# Tiny84_board.net
KiCad netlist of a schematic drawn in EAGLE
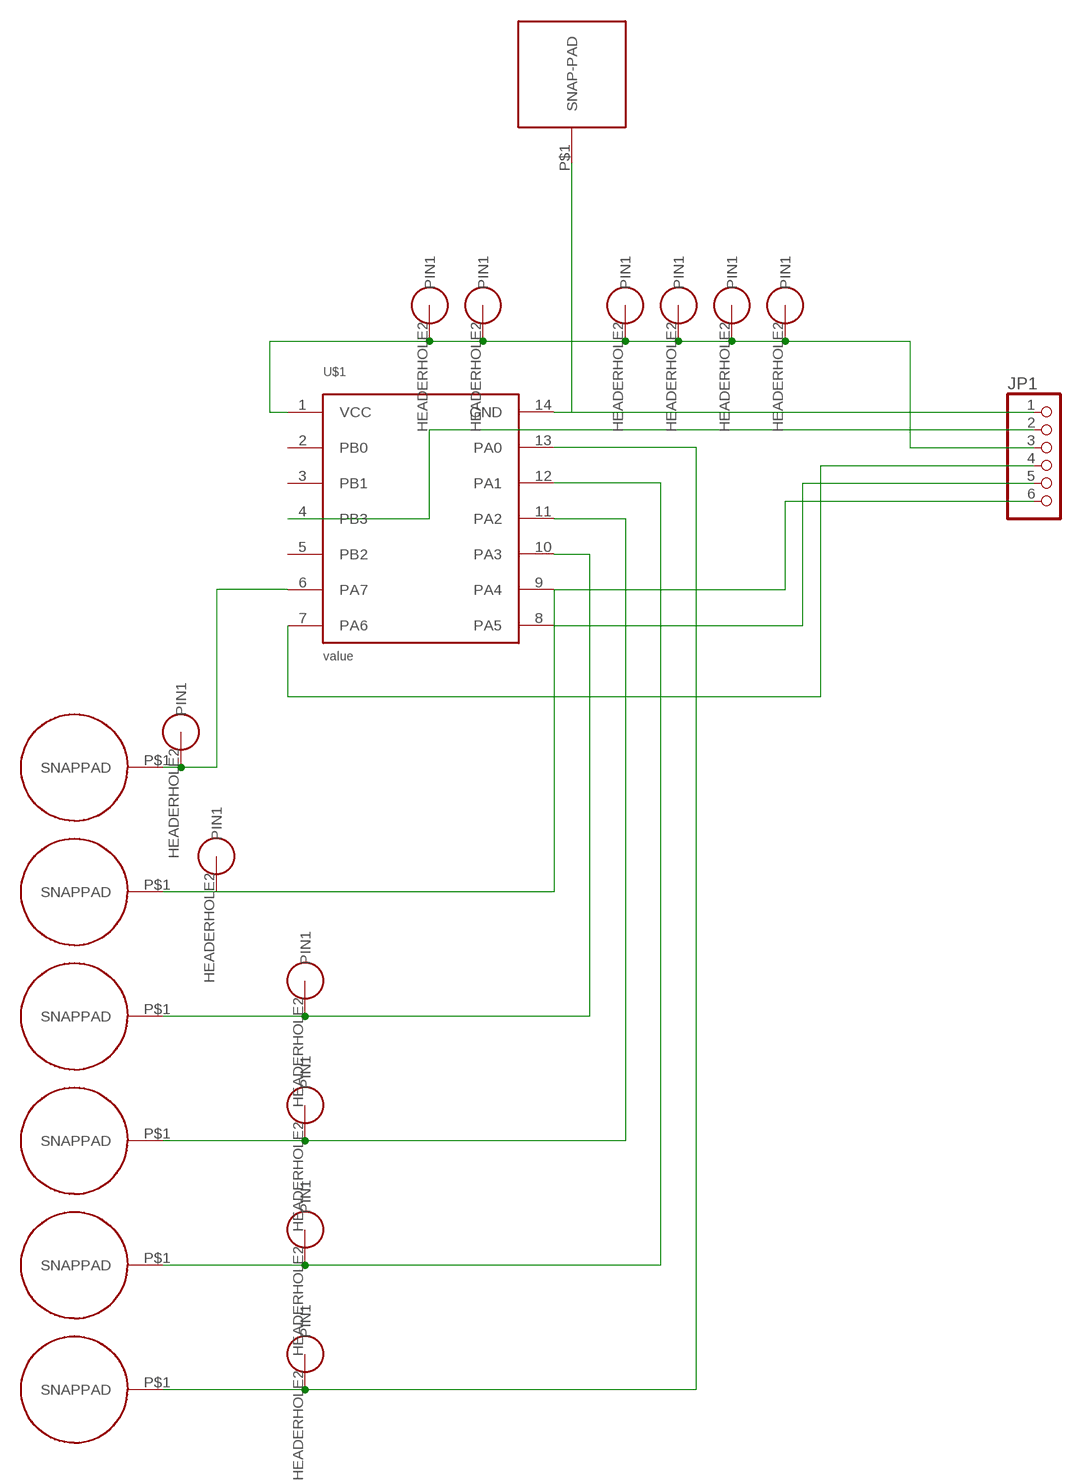
[diagram p0: schematic, sheet 1]

(export (version "E")
  (design (tool "Eeschema 10.0.6"))
  (components
    (comp (ref "JP1")
      (value "PINHD-1X6/90")
      (footprint "eagle-import:1X06_90")
      (libsource (lib "eagle-import") (part "PINHD-1X6/90"))
    )
    (comp (ref "U$1")
      (value "ATTINY84")
      (footprint "eagle-import:SOIC14")
      (libsource (lib "eagle-import") (part "ATTINY84"))
    )
    (comp (ref "U$2")
      (value "SNAP-PAD_7MM_ROUND")
      (footprint "eagle-import:SNAP-PAD_7MM_RD")
      (libsource (lib "eagle-import") (part "SNAP-PAD_7MM_ROUND"))
    )
    (comp (ref "U$3")
      (value "SNAP-PAD_7MM_ROUND")
      (footprint "eagle-import:SNAP-PAD_7MM_RD")
      (libsource (lib "eagle-import") (part "SNAP-PAD_7MM_ROUND"))
    )
    (comp (ref "U$4")
      (value "SNAP-PAD_7MM_ROUND")
      (footprint "eagle-import:SNAP-PAD_7MM_RD")
      (libsource (lib "eagle-import") (part "SNAP-PAD_7MM_ROUND"))
    )
    (comp (ref "U$5")
      (value "SNAP-PAD_7MM_ROUND")
      (footprint "eagle-import:SNAP-PAD_7MM_RD")
      (libsource (lib "eagle-import") (part "SNAP-PAD_7MM_ROUND"))
    )
    (comp (ref "U$6")
      (value "SNAP-PAD_7MM_ROUND")
      (footprint "eagle-import:SNAP-PAD_7MM_RD")
      (libsource (lib "eagle-import") (part "SNAP-PAD_7MM_ROUND"))
    )
    (comp (ref "U$7")
      (value "SNAP-PAD_7MM_ROUND")
      (footprint "eagle-import:SNAP-PAD_7MM_RD")
      (libsource (lib "eagle-import") (part "SNAP-PAD_7MM_ROUND"))
    )
    (comp (ref "U$14")
      (value "SNAP-PAD_7MM_SQUARE")
      (footprint "eagle-import:SNAP-PAD_7MM_SQ")
      (libsource (lib "eagle-import") (part "SNAP-PAD_7MM_SQUARE"))
    )
    (comp (ref "U$15")
      (value "HEADER_1PIN")
      (footprint "eagle-import:HEADER_1PIN")
      (libsource (lib "eagle-import") (part "HEADER_1PIN"))
    )
    (comp (ref "U$16")
      (value "HEADER_1PIN")
      (footprint "eagle-import:HEADER_1PIN")
      (libsource (lib "eagle-import") (part "HEADER_1PIN"))
    )
    (comp (ref "U$17")
      (value "HEADER_1PIN")
      (footprint "eagle-import:HEADER_1PIN")
      (libsource (lib "eagle-import") (part "HEADER_1PIN"))
    )
    (comp (ref "U$19")
      (value "HEADER_1PIN")
      (footprint "eagle-import:HEADER_1PIN")
      (libsource (lib "eagle-import") (part "HEADER_1PIN"))
    )
    (comp (ref "U$20")
      (value "HEADER_1PIN")
      (footprint "eagle-import:HEADER_1PIN")
      (libsource (lib "eagle-import") (part "HEADER_1PIN"))
    )
    (comp (ref "U$21")
      (value "HEADER_1PIN")
      (footprint "eagle-import:HEADER_1PIN")
      (libsource (lib "eagle-import") (part "HEADER_1PIN"))
    )
    (comp (ref "U$24")
      (value "HEADER_1PIN")
      (footprint "eagle-import:HEADER_1PIN")
      (libsource (lib "eagle-import") (part "HEADER_1PIN"))
    )
    (comp (ref "U$25")
      (value "HEADER_1PIN")
      (footprint "eagle-import:HEADER_1PIN")
      (libsource (lib "eagle-import") (part "HEADER_1PIN"))
    )
    (comp (ref "U$26")
      (value "HEADER_1PIN")
      (footprint "eagle-import:HEADER_1PIN")
      (libsource (lib "eagle-import") (part "HEADER_1PIN"))
    )
    (comp (ref "U$27")
      (value "HEADER_1PIN")
      (footprint "eagle-import:HEADER_1PIN")
      (libsource (lib "eagle-import") (part "HEADER_1PIN"))
    )
    (comp (ref "U$30")
      (value "HEADER_1PIN")
      (footprint "eagle-import:HEADER_1PIN")
      (libsource (lib "eagle-import") (part "HEADER_1PIN"))
    )
    (comp (ref "U$31")
      (value "HEADER_1PIN")
      (footprint "eagle-import:HEADER_1PIN")
      (libsource (lib "eagle-import") (part "HEADER_1PIN"))
    )
  )
  (nets
    (net (code "1") (name "Net-(U$1-GND)") (class "Default")
      (node (ref "JP1") (pin "1") (pinfunction "1_1") (pintype "passive"))
      (node (ref "U$1") (pin "14") (pinfunction "GND_14") (pintype "bidirectional"))
      (node (ref "U$14") (pin "P$1") (pinfunction "SNAP-PAD_P$1") (pintype "bidirectional"))
    )
    (net (code "2") (name "Net-(U$1-PA0)") (class "Default")
      (node (ref "U$1") (pin "13") (pinfunction "PA0_13") (pintype "bidirectional"))
      (node (ref "U$21") (pin "HEADERHOLE2") (pinfunction "PIN1_HEADERHOLE2") (pintype "bidirectional"))
      (node (ref "U$7") (pin "P$1") (pinfunction "SNAPPAD_P$1") (pintype "bidirectional"))
    )
    (net (code "3") (name "Net-(U$1-PA1)") (class "Default")
      (node (ref "U$1") (pin "12") (pinfunction "PA1_12") (pintype "bidirectional"))
      (node (ref "U$20") (pin "HEADERHOLE2") (pinfunction "PIN1_HEADERHOLE2") (pintype "bidirectional"))
      (node (ref "U$6") (pin "P$1") (pinfunction "SNAPPAD_P$1") (pintype "bidirectional"))
    )
    (net (code "4") (name "Net-(U$1-PA2)") (class "Default")
      (node (ref "U$1") (pin "11") (pinfunction "PA2_11") (pintype "bidirectional"))
      (node (ref "U$19") (pin "HEADERHOLE2") (pinfunction "PIN1_HEADERHOLE2") (pintype "bidirectional"))
      (node (ref "U$5") (pin "P$1") (pinfunction "SNAPPAD_P$1") (pintype "bidirectional"))
    )
    (net (code "5") (name "Net-(U$1-PA3)") (class "Default")
      (node (ref "U$1") (pin "10") (pinfunction "PA3_10") (pintype "bidirectional"))
      (node (ref "U$17") (pin "HEADERHOLE2") (pinfunction "PIN1_HEADERHOLE2") (pintype "bidirectional"))
      (node (ref "U$4") (pin "P$1") (pinfunction "SNAPPAD_P$1") (pintype "bidirectional"))
    )
    (net (code "6") (name "Net-(U$1-PA4)") (class "Default")
      (node (ref "JP1") (pin "6") (pinfunction "6_6") (pintype "passive"))
      (node (ref "U$1") (pin "9") (pinfunction "PA4_9") (pintype "bidirectional"))
      (node (ref "U$26") (pin "HEADERHOLE2") (pinfunction "PIN1_HEADERHOLE2") (pintype "bidirectional"))
      (node (ref "U$3") (pin "P$1") (pinfunction "SNAPPAD_P$1") (pintype "bidirectional"))
    )
    (net (code "7") (name "Net-(U$1-PA5)") (class "Default")
      (node (ref "JP1") (pin "5") (pinfunction "5_5") (pintype "passive"))
      (node (ref "U$1") (pin "8") (pinfunction "PA5_8") (pintype "bidirectional"))
    )
    (net (code "8") (name "Net-(U$1-PA6)") (class "Default")
      (node (ref "JP1") (pin "4") (pinfunction "4_4") (pintype "passive"))
      (node (ref "U$1") (pin "7") (pinfunction "PA6_7") (pintype "bidirectional"))
    )
    (net (code "9") (name "Net-(U$1-PA7)") (class "Default")
      (node (ref "U$1") (pin "6") (pinfunction "PA7_6") (pintype "bidirectional"))
      (node (ref "U$2") (pin "P$1") (pinfunction "SNAPPAD_P$1") (pintype "bidirectional"))
      (node (ref "U$27") (pin "HEADERHOLE2") (pinfunction "PIN1_HEADERHOLE2") (pintype "bidirectional"))
    )
    (net (code "10") (name "Net-(U$1-PB3)") (class "Default")
      (node (ref "JP1") (pin "2") (pinfunction "2_2") (pintype "passive"))
      (node (ref "U$1") (pin "4") (pinfunction "PB3_4") (pintype "bidirectional"))
    )
    (net (code "11") (name "Net-(U$1-VCC)") (class "Default")
      (node (ref "JP1") (pin "3") (pinfunction "3_3") (pintype "passive"))
      (node (ref "U$1") (pin "1") (pinfunction "VCC_1") (pintype "bidirectional"))
      (node (ref "U$15") (pin "HEADERHOLE2") (pinfunction "PIN1_HEADERHOLE2") (pintype "bidirectional"))
      (node (ref "U$16") (pin "HEADERHOLE2") (pinfunction "PIN1_HEADERHOLE2") (pintype "bidirectional"))
      (node (ref "U$24") (pin "HEADERHOLE2") (pinfunction "PIN1_HEADERHOLE2") (pintype "bidirectional"))
      (node (ref "U$25") (pin "HEADERHOLE2") (pinfunction "PIN1_HEADERHOLE2") (pintype "bidirectional"))
      (node (ref "U$30") (pin "HEADERHOLE2") (pinfunction "PIN1_HEADERHOLE2") (pintype "bidirectional"))
      (node (ref "U$31") (pin "HEADERHOLE2") (pinfunction "PIN1_HEADERHOLE2") (pintype "bidirectional"))
    )
    (net (code "12") (name "unconnected-(U$1-PB0-Pad2)") (class "Default")
      (node (ref "U$1") (pin "2") (pinfunction "PB0_2") (pintype "bidirectional"))
    )
    (net (code "13") (name "unconnected-(U$1-PB1-Pad3)") (class "Default")
      (node (ref "U$1") (pin "3") (pinfunction "PB1_3") (pintype "bidirectional"))
    )
    (net (code "14") (name "unconnected-(U$1-PB2-Pad5)") (class "Default")
      (node (ref "U$1") (pin "5") (pinfunction "PB2_5") (pintype "bidirectional"))
    )
  )
)
